# 07_-_DEBUGGING_PROGRAMMING.net
KiCad netlist of a schematic drawn in Altium Designer
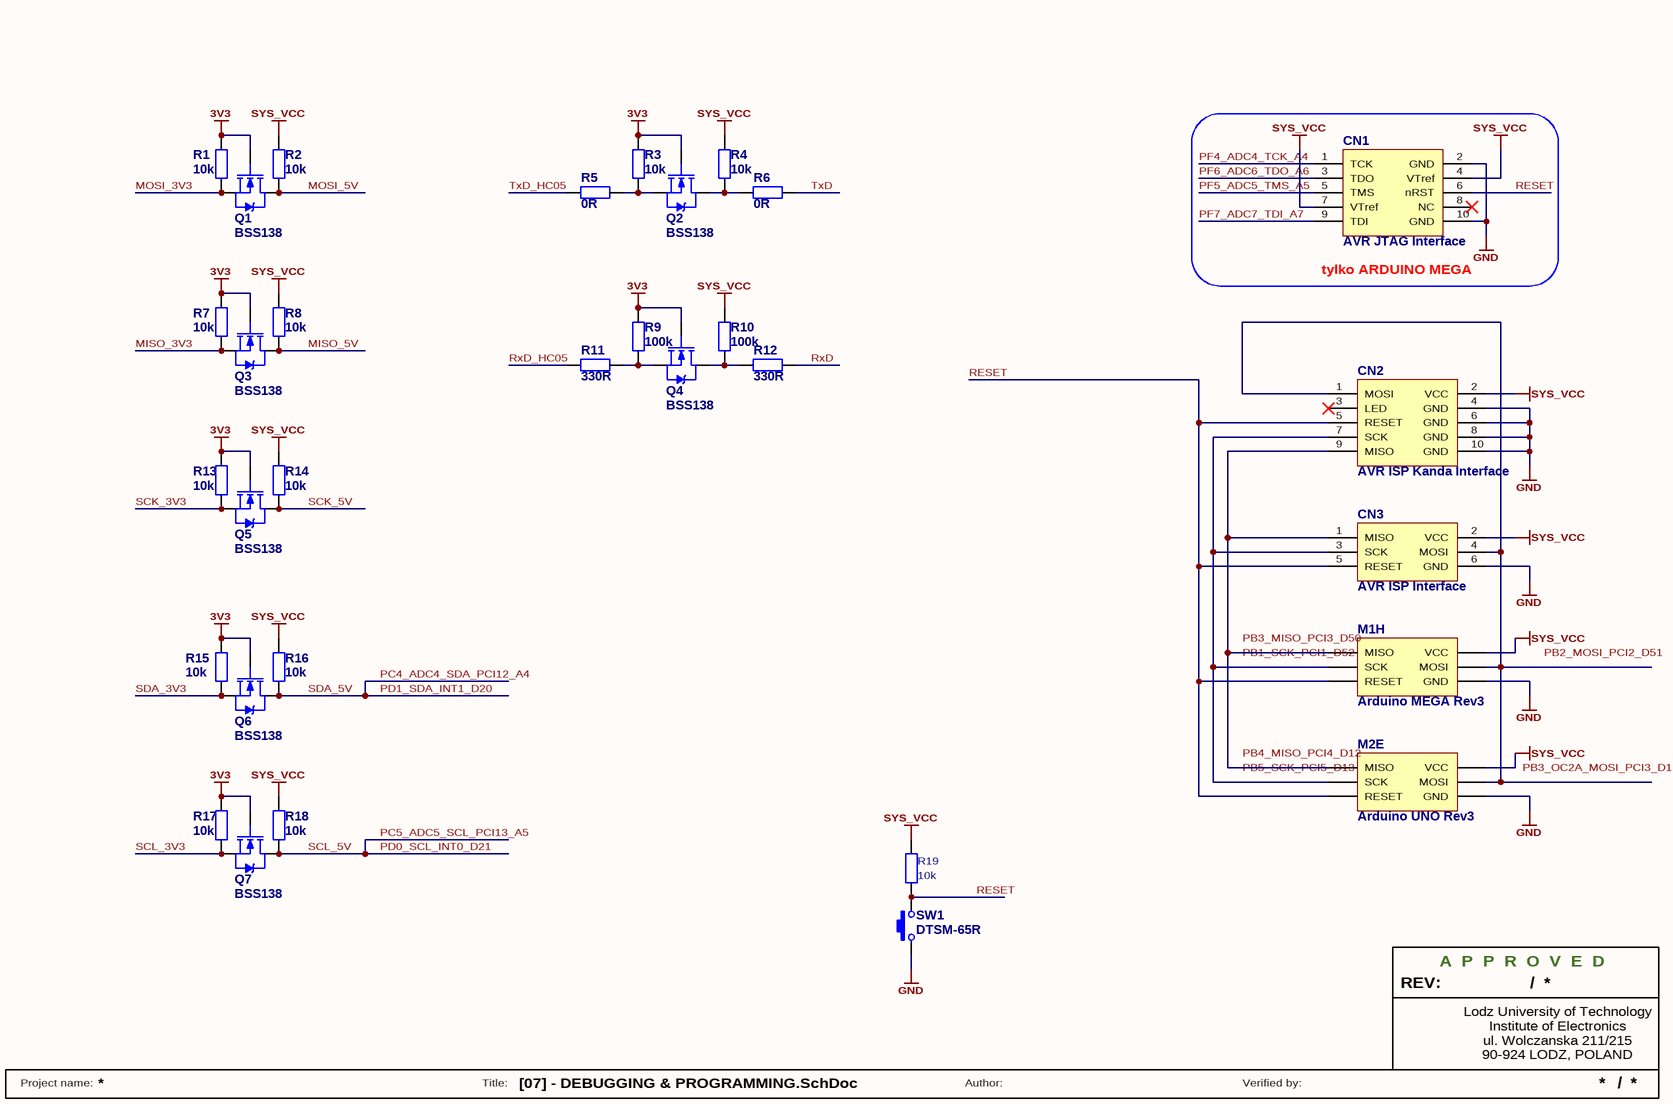
[diagram p0: [07] - DEBUGGING & PROGRAMMING.SchDoc]

(export (version "E")
  (design (tool "Eeschema 10.0.6"))
  (components
    (comp (ref "CN1")
      (value "AVR JTAG Interface")
      (footprint "IDC10")
      (description "JTAG Header for AVR MCU's")
      (libsource (lib "mcu_prog_and_debug_connectors") (part "AVR JTAG Interface"))
    )
    (comp (ref "CN2")
      (value "AVR ISP Kanda Interface")
      (footprint "IDC10")
      (description "Kanda ISP Programming Header for AVR MCU's")
      (libsource (lib "mcu_prog_and_debug_connectors") (part "AVR ISP Kanda Interface"))
    )
    (comp (ref "CN3")
      (value "AVR ISP Interface")
      (footprint "IDC6")
      (description "ISP Programming Header for AVR MCU's")
      (libsource (lib "mcu_prog_and_debug_connectors") (part "AVR ISP Interface"))
    )
    (comp (ref "M1")
      (value "Arduino MEGA Rev3")
      (footprint "Arduino_MEGA_UPSIDE_DOWN")
      (description "Arduino MEGA Rev3 Board")
      (libsource (lib "mcu_modules") (part "Arduino MEGA Rev3"))
    )
    (comp (ref "M2")
      (value "Arduino UNO Rev3")
      (footprint "Arduino_UNO_UPSIDE_DOWN")
      (description "Arduino UNO Rev3 Board")
      (libsource (lib "mcu_modules") (part "Arduino UNO Rev3"))
    )
    (comp (ref "Q1")
      (value "BSS138")
      (footprint "SOT-23")
      (description "N-Channel Enhancement Mode Vertical DMOS FET")
      (fields (field (name "PUBLISHER") "Altium Limited"))
      (libsource (lib "transistors_other") (part "BSS138"))
    )
    (comp (ref "Q2")
      (value "BSS138")
      (footprint "SOT-23")
      (description "N-Channel Enhancement Mode Vertical DMOS FET")
      (fields (field (name "PUBLISHER") "Altium Limited"))
      (libsource (lib "transistors_mos") (part "BSS138"))
    )
    (comp (ref "Q3")
      (value "BSS138")
      (footprint "SOT-23")
      (description "N-Channel Enhancement Mode Vertical DMOS FET")
      (fields (field (name "PUBLISHER") "Altium Limited"))
      (libsource (lib "transistors_other") (part "BSS138"))
    )
    (comp (ref "Q4")
      (value "BSS138")
      (footprint "SOT-23")
      (description "N-Channel Enhancement Mode Vertical DMOS FET")
      (fields (field (name "PUBLISHER") "Altium Limited"))
      (libsource (lib "transistors_mos") (part "BSS138"))
    )
    (comp (ref "Q5")
      (value "BSS138")
      (footprint "SOT-23")
      (description "N-Channel Enhancement Mode Vertical DMOS FET")
      (fields (field (name "PUBLISHER") "Altium Limited"))
      (libsource (lib "transistors_other") (part "BSS138"))
    )
    (comp (ref "Q6")
      (value "BSS138")
      (footprint "SOT-23")
      (description "N-Channel Enhancement Mode Vertical DMOS FET")
      (fields (field (name "PUBLISHER") "Altium Limited"))
      (libsource (lib "transistors_other") (part "BSS138"))
    )
    (comp (ref "Q7")
      (value "BSS138")
      (footprint "SOT-23")
      (description "N-Channel Enhancement Mode Vertical DMOS FET")
      (fields (field (name "PUBLISHER") "Altium Limited"))
      (libsource (lib "transistors_other") (part "BSS138"))
    )
    (comp (ref "R1")
      (value "10k")
      (footprint "R0805")
      (description "Resistor")
      (libsource (lib "resistors") (part "Res"))
    )
    (comp (ref "R2")
      (value "10k")
      (footprint "R0805")
      (description "Resistor")
      (libsource (lib "resistors") (part "Res"))
    )
    (comp (ref "R3")
      (value "10k")
      (footprint "R0805")
      (description "Resistor")
      (libsource (lib "") (part "Res_2"))
    )
    (comp (ref "R4")
      (value "10k")
      (footprint "R0805")
      (description "Resistor")
      (libsource (lib "") (part "Res_2"))
    )
    (comp (ref "R5")
      (value "0R")
      (footprint "R0805")
      (description "Resistor")
      (libsource (lib "") (part "Res_3"))
    )
    (comp (ref "R6")
      (value "0R")
      (footprint "R0805")
      (description "Resistor")
      (libsource (lib "") (part "Res_3"))
    )
    (comp (ref "R7")
      (value "10k")
      (footprint "R0805")
      (description "Resistor")
      (libsource (lib "resistors") (part "Res"))
    )
    (comp (ref "R8")
      (value "10k")
      (footprint "R0805")
      (description "Resistor")
      (libsource (lib "resistors") (part "Res"))
    )
    (comp (ref "R9")
      (value "100k")
      (footprint "R0805")
      (description "Resistor")
      (libsource (lib "") (part "Res_2"))
    )
    (comp (ref "R10")
      (value "100k")
      (footprint "R0805")
      (description "Resistor")
      (libsource (lib "") (part "Res_2"))
    )
    (comp (ref "R11")
      (value "330R")
      (footprint "R0805")
      (description "Resistor")
      (libsource (lib "") (part "Res_3"))
    )
    (comp (ref "R12")
      (value "330R")
      (footprint "R0805")
      (description "Resistor")
      (libsource (lib "") (part "Res_3"))
    )
    (comp (ref "R13")
      (value "10k")
      (footprint "R0805")
      (description "Resistor")
      (libsource (lib "resistors") (part "Res"))
    )
    (comp (ref "R14")
      (value "10k")
      (footprint "R0805")
      (description "Resistor")
      (libsource (lib "resistors") (part "Res"))
    )
    (comp (ref "R15")
      (value "10k")
      (footprint "R0805")
      (description "Resistor")
      (libsource (lib "resistors") (part "Res"))
    )
    (comp (ref "R16")
      (value "10k")
      (footprint "R0805")
      (description "Resistor")
      (libsource (lib "resistors") (part "Res"))
    )
    (comp (ref "R17")
      (value "10k")
      (footprint "R0805")
      (description "Resistor")
      (libsource (lib "resistors") (part "Res"))
    )
    (comp (ref "R18")
      (value "10k")
      (footprint "R0805")
      (description "Resistor")
      (libsource (lib "resistors") (part "Res"))
    )
    (comp (ref "R19")
      (value "10k")
      (footprint "R0805")
      (description "Resistor")
      (libsource (lib "") (part "Res_1"))
    )
    (comp (ref "SW1")
      (value "DTSM-65R")
      (footprint "DTSM-65R")
      (description "DIPTRONICS Red 6x6mm SMD Tactile SPST-NO Switch")
      (libsource (lib "microswitches") (part "DTSM-65R"))
    )
  )
  (nets
    (net (code "1") (name "/MISO_3V3") (class "Default")
      (node (ref "Q3") (pin "2") (pinfunction "S_2") (pintype "passive"))
      (node (ref "R7") (pin "1") (pinfunction "1_1") (pintype "passive"))
    )
    (net (code "2") (name "/MISO_5V") (class "Default")
      (node (ref "Q3") (pin "3") (pinfunction "D_3") (pintype "passive"))
      (node (ref "R8") (pin "1") (pinfunction "1_1") (pintype "passive"))
    )
    (net (code "3") (name "/MOSI_3V3") (class "Default")
      (node (ref "Q1") (pin "2") (pinfunction "S_2") (pintype "passive"))
      (node (ref "R1") (pin "1") (pinfunction "1_1") (pintype "passive"))
    )
    (net (code "4") (name "/MOSI_5V") (class "Default")
      (node (ref "Q1") (pin "3") (pinfunction "D_3") (pintype "passive"))
      (node (ref "R2") (pin "1") (pinfunction "1_1") (pintype "passive"))
    )
    (net (code "11") (name "/PC4_ADC4_SDA_PCI12_A4") (class "Default")
      (node (ref "Q6") (pin "3") (pinfunction "D_3") (pintype "passive"))
      (node (ref "R16") (pin "1") (pinfunction "1_1") (pintype "passive"))
    )
    (net (code "12") (name "/PC5_ADC5_SCL_PCI13_A5") (class "Default")
      (node (ref "Q7") (pin "3") (pinfunction "D_3") (pintype "passive"))
      (node (ref "R18") (pin "1") (pinfunction "1_1") (pintype "passive"))
    )
    (net (code "13") (name "/PF4_ADC4_TCK_A4") (class "Default")
      (node (ref "CN1") (pin "1") (pinfunction "TCK_1") (pintype "passive"))
    )
    (net (code "14") (name "/PF5_ADC5_TMS_A5") (class "Default")
      (node (ref "CN1") (pin "5") (pinfunction "TMS_5") (pintype "passive"))
    )
    (net (code "15") (name "/PF6_ADC6_TDO_A6") (class "Default")
      (node (ref "CN1") (pin "3") (pinfunction "TDO_3") (pintype "passive"))
    )
    (net (code "16") (name "/PF7_ADC7_TDI_A7") (class "Default")
      (node (ref "CN1") (pin "9") (pinfunction "TDI_9") (pintype "passive"))
    )
    (net (code "17") (name "/RESET") (class "Default")
      (node (ref "CN1") (pin "6") (pinfunction "nRST_6") (pintype "passive"))
      (node (ref "CN2") (pin "5") (pinfunction "RESET_5") (pintype "passive"))
      (node (ref "CN3") (pin "5") (pinfunction "RESET_5") (pintype "passive"))
      (node (ref "M1") (pin "PROG5") (pinfunction "RESET_PROG5") (pintype "passive"))
      (node (ref "M2") (pin "PROG5") (pinfunction "RESET_PROG5") (pintype "passive"))
      (node (ref "R19") (pin "1") (pinfunction "1_1") (pintype "passive"))
      (node (ref "SW1") (pin "2") (pinfunction "2_2") (pintype "passive"))
    )
    (net (code "18") (name "/RxD") (class "Default")
      (node (ref "R12") (pin "2") (pinfunction "2_2") (pintype "passive"))
    )
    (net (code "19") (name "/RxD_HC05") (class "Default")
      (node (ref "R11") (pin "1") (pinfunction "1_1") (pintype "passive"))
    )
    (net (code "20") (name "/SCK_3V3") (class "Default")
      (node (ref "Q5") (pin "2") (pinfunction "S_2") (pintype "passive"))
      (node (ref "R13") (pin "1") (pinfunction "1_1") (pintype "passive"))
    )
    (net (code "21") (name "/SCK_5V") (class "Default")
      (node (ref "Q5") (pin "3") (pinfunction "D_3") (pintype "passive"))
      (node (ref "R14") (pin "1") (pinfunction "1_1") (pintype "passive"))
    )
    (net (code "22") (name "/SCL_3V3") (class "Default")
      (node (ref "Q7") (pin "2") (pinfunction "S_2") (pintype "passive"))
      (node (ref "R17") (pin "1") (pinfunction "1_1") (pintype "passive"))
    )
    (net (code "23") (name "/SDA_3V3") (class "Default")
      (node (ref "Q6") (pin "2") (pinfunction "S_2") (pintype "passive"))
      (node (ref "R15") (pin "1") (pinfunction "1_1") (pintype "passive"))
    )
    (net (code "24") (name "/TxD") (class "Default")
      (node (ref "R6") (pin "2") (pinfunction "2_2") (pintype "passive"))
    )
    (net (code "25") (name "/TxD_HC05") (class "Default")
      (node (ref "R5") (pin "1") (pinfunction "1_1") (pintype "passive"))
    )
    (net (code "26") (name "3V3") (class "Default")
      (node (ref "Q1") (pin "1") (pinfunction "G_1") (pintype "passive"))
      (node (ref "Q2") (pin "1") (pinfunction "G_1") (pintype "passive"))
      (node (ref "Q3") (pin "1") (pinfunction "G_1") (pintype "passive"))
      (node (ref "Q4") (pin "1") (pinfunction "G_1") (pintype "passive"))
      (node (ref "Q5") (pin "1") (pinfunction "G_1") (pintype "passive"))
      (node (ref "Q6") (pin "1") (pinfunction "G_1") (pintype "passive"))
      (node (ref "Q7") (pin "1") (pinfunction "G_1") (pintype "passive"))
      (node (ref "R1") (pin "2") (pinfunction "2_2") (pintype "passive"))
      (node (ref "R13") (pin "2") (pinfunction "2_2") (pintype "passive"))
      (node (ref "R15") (pin "2") (pinfunction "2_2") (pintype "passive"))
      (node (ref "R17") (pin "2") (pinfunction "2_2") (pintype "passive"))
      (node (ref "R3") (pin "1") (pinfunction "1_1") (pintype "passive"))
      (node (ref "R7") (pin "2") (pinfunction "2_2") (pintype "passive"))
      (node (ref "R9") (pin "1") (pinfunction "1_1") (pintype "passive"))
    )
    (net (code "27") (name "GND") (class "Default")
      (node (ref "CN1") (pin "10") (pinfunction "GND_10") (pintype "passive"))
      (node (ref "CN1") (pin "2") (pinfunction "GND_2") (pintype "passive"))
      (node (ref "CN2") (pin "10") (pinfunction "GND_10") (pintype "passive"))
      (node (ref "CN2") (pin "4") (pinfunction "GND_4") (pintype "passive"))
      (node (ref "CN2") (pin "6") (pinfunction "GND_6") (pintype "passive"))
      (node (ref "CN2") (pin "8") (pinfunction "GND_8") (pintype "passive"))
      (node (ref "CN3") (pin "6") (pinfunction "GND_6") (pintype "passive"))
      (node (ref "M1") (pin "PROG6") (pinfunction "GND_PROG6") (pintype "passive"))
      (node (ref "M2") (pin "PROG6") (pinfunction "GND_PROG6") (pintype "passive"))
      (node (ref "SW1") (pin "1") (pinfunction "1_1") (pintype "passive"))
    )
    (net (code "28") (name "Net-(CN2-MISO)") (class "Default")
      (node (ref "CN2") (pin "9") (pinfunction "MISO_9") (pintype "passive"))
      (node (ref "CN3") (pin "1") (pinfunction "MISO_1") (pintype "passive"))
      (node (ref "M1") (pin "PROG1") (pinfunction "MISO_PROG1") (pintype "passive"))
      (node (ref "M2") (pin "PROG1") (pinfunction "MISO_PROG1") (pintype "passive"))
    )
    (net (code "29") (name "Net-(CN2-MOSI)") (class "Default")
      (node (ref "CN2") (pin "1") (pinfunction "MOSI_1") (pintype "passive"))
      (node (ref "CN3") (pin "4") (pinfunction "MOSI_4") (pintype "passive"))
      (node (ref "M1") (pin "PROG4") (pinfunction "MOSI_PROG4") (pintype "passive"))
      (node (ref "M2") (pin "PROG4") (pinfunction "MOSI_PROG4") (pintype "passive"))
    )
    (net (code "30") (name "Net-(CN2-SCK)") (class "Default")
      (node (ref "CN2") (pin "7") (pinfunction "SCK_7") (pintype "passive"))
      (node (ref "CN3") (pin "3") (pinfunction "SCK_3") (pintype "passive"))
      (node (ref "M1") (pin "PROG3") (pinfunction "SCK_PROG3") (pintype "passive"))
      (node (ref "M2") (pin "PROG3") (pinfunction "SCK_PROG3") (pintype "passive"))
    )
    (net (code "31") (name "Net-(Q2-D)") (class "Default")
      (node (ref "Q2") (pin "3") (pinfunction "D_3") (pintype "passive"))
      (node (ref "R4") (pin "2") (pinfunction "2_2") (pintype "passive"))
      (node (ref "R6") (pin "1") (pinfunction "1_1") (pintype "passive"))
    )
    (net (code "32") (name "Net-(Q2-S)") (class "Default")
      (node (ref "Q2") (pin "2") (pinfunction "S_2") (pintype "passive"))
      (node (ref "R3") (pin "2") (pinfunction "2_2") (pintype "passive"))
      (node (ref "R5") (pin "2") (pinfunction "2_2") (pintype "passive"))
    )
    (net (code "33") (name "Net-(Q4-D)") (class "Default")
      (node (ref "Q4") (pin "3") (pinfunction "D_3") (pintype "passive"))
      (node (ref "R10") (pin "2") (pinfunction "2_2") (pintype "passive"))
      (node (ref "R12") (pin "1") (pinfunction "1_1") (pintype "passive"))
    )
    (net (code "34") (name "Net-(Q4-S)") (class "Default")
      (node (ref "Q4") (pin "2") (pinfunction "S_2") (pintype "passive"))
      (node (ref "R11") (pin "2") (pinfunction "2_2") (pintype "passive"))
      (node (ref "R9") (pin "2") (pinfunction "2_2") (pintype "passive"))
    )
    (net (code "35") (name "SYS_VCC") (class "Default")
      (node (ref "CN1") (pin "4") (pinfunction "VTref_4") (pintype "passive"))
      (node (ref "CN1") (pin "7") (pinfunction "VTref_7") (pintype "passive"))
      (node (ref "CN2") (pin "2") (pinfunction "VCC_2") (pintype "passive"))
      (node (ref "CN3") (pin "2") (pinfunction "VCC_2") (pintype "passive"))
      (node (ref "M1") (pin "PROG2") (pinfunction "VCC_PROG2") (pintype "passive"))
      (node (ref "M2") (pin "PROG2") (pinfunction "VCC_PROG2") (pintype "passive"))
      (node (ref "R10") (pin "1") (pinfunction "1_1") (pintype "passive"))
      (node (ref "R14") (pin "2") (pinfunction "2_2") (pintype "passive"))
      (node (ref "R16") (pin "2") (pinfunction "2_2") (pintype "passive"))
      (node (ref "R18") (pin "2") (pinfunction "2_2") (pintype "passive"))
      (node (ref "R19") (pin "2") (pinfunction "2_2") (pintype "passive"))
      (node (ref "R2") (pin "2") (pinfunction "2_2") (pintype "passive"))
      (node (ref "R4") (pin "1") (pinfunction "1_1") (pintype "passive"))
      (node (ref "R8") (pin "2") (pinfunction "2_2") (pintype "passive"))
    )
    (net (code "36") (name "unconnected-(CN1-NC-Pad8)") (class "Default")
      (node (ref "CN1") (pin "8") (pinfunction "NC_8") (pintype "passive+no_connect"))
    )
    (net (code "37") (name "unconnected-(CN2-LED-Pad3)") (class "Default")
      (node (ref "CN2") (pin "3") (pinfunction "LED_3") (pintype "passive+no_connect"))
    )
  )
)
